# RTC_Clock.net
KiCad netlist of a schematic drawn in Altium Designer
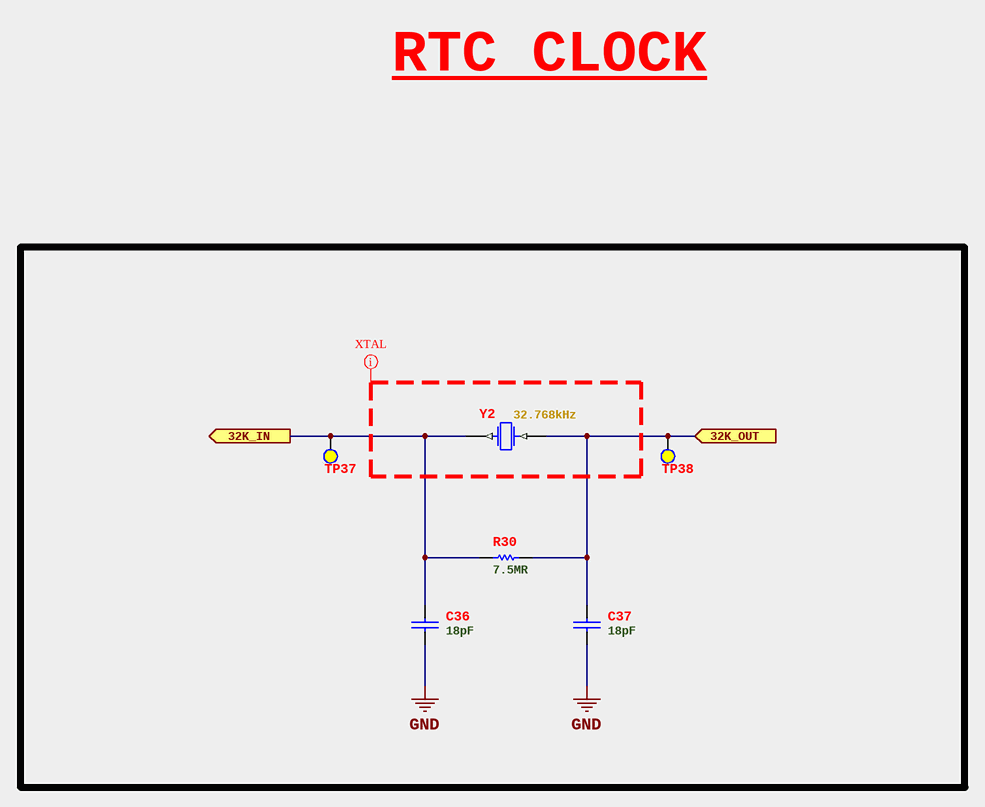
[diagram p0: RTC Clock.SchDoc]

(export (version "E")
  (design (tool "Eeschema 10.0.6"))
  (components
    (comp (ref "C36")
      (value "18pF")
      (footprint "CAP_0603")
      (description "18 pF ±1% 50V Ceramic Capacitor C0G, NP0 0603 (1608 Metric)")
      (fields
        (field (name "MANUFACTURER") "Yageo")
        (field (name "MANUFACTURER PART NUMBER") "CC0603FRNPO9BN180")
      )
      (libsource (lib "Cellar Watchdog") (part "CAP_18pf-50V-1%_0603"))
    )
    (comp (ref "C37")
      (value "18pF")
      (footprint "CAP_0603")
      (description "18 pF ±1% 50V Ceramic Capacitor C0G, NP0 0603 (1608 Metric)")
      (fields
        (field (name "MANUFACTURER") "Yageo")
        (field (name "MANUFACTURER PART NUMBER") "CC0603FRNPO9BN180")
      )
      (libsource (lib "Cellar Watchdog") (part "CAP_18pf-50V-1%_0603"))
    )
    (comp (ref "R30")
      (value "7.5MR")
      (footprint "RES_0603")
      (description "7.5 MOhms ±1% 0.1W, 1/10W Chip Resistor 0603 (1608 Metric) Moisture Resistant Thick Film")
      (fields
        (field (name "MANUFACTURER") "Yageo")
        (field (name "MANUFACTURER PART NUMBER") "RC0603FR-077M5L")
      )
      (libsource (lib "Cellar Watchdog") (part "RES_7.5MR-100mW-1%_0603"))
    )
    (comp (ref "TP37")
      (value "RTC 32.768KHz IN")
      (footprint "TEST POINT HOLE")
      (description "PCB Test Point")
      (libsource (lib "Cellar Watchdog") (part "Test Point"))
    )
    (comp (ref "TP38")
      (value "RTC 32.768KHz OUT")
      (footprint "TEST POINT HOLE")
      (description "PCB Test Point")
      (libsource (lib "Cellar Watchdog") (part "Test Point"))
    )
    (comp (ref "Y2")
      (value "ECX-.327-CDX-1293")
      (footprint "XTAL_ECX-.327-CDX-1293")
      (description "32.768 kHz ±5ppm Crystal 12.5pF 70 kOhms 2-SMD, No Lead")
      (fields (field (name "MANUFACTURER") "ECS International") (field (name "FREQUENCY") "32.768kHz"))
      (libsource (lib "Cellar Watchdog") (part "XTAL_32.768KHz-12.5pF_2-SMD"))
    )
  )
  (nets
    (net (code "1") (name "/32K_IN") (class "Default")
      (node (ref "C36") (pin "1") (pinfunction "1_1") (pintype "passive"))
      (node (ref "R30") (pin "1") (pinfunction "1_1") (pintype "passive"))
      (node (ref "TP37") (pin "TP") (pinfunction "TP_TP") (pintype "passive"))
      (node (ref "Y2") (pin "1") (pinfunction "In/Out_1") (pintype "output"))
    )
    (net (code "2") (name "/32K_OUT") (class "Default")
      (node (ref "C37") (pin "1") (pinfunction "1_1") (pintype "passive"))
      (node (ref "R30") (pin "2") (pinfunction "2_2") (pintype "passive"))
      (node (ref "TP38") (pin "TP") (pinfunction "TP_TP") (pintype "passive"))
      (node (ref "Y2") (pin "2") (pinfunction "Out/In_2") (pintype "input"))
    )
    (net (code "3") (name "GND") (class "Default")
      (node (ref "C36") (pin "2") (pinfunction "2_2") (pintype "passive"))
      (node (ref "C37") (pin "2") (pinfunction "2_2") (pintype "passive"))
    )
  )
)
